# DLOCK.net
KiCad netlist of a schematic drawn in EAGLE
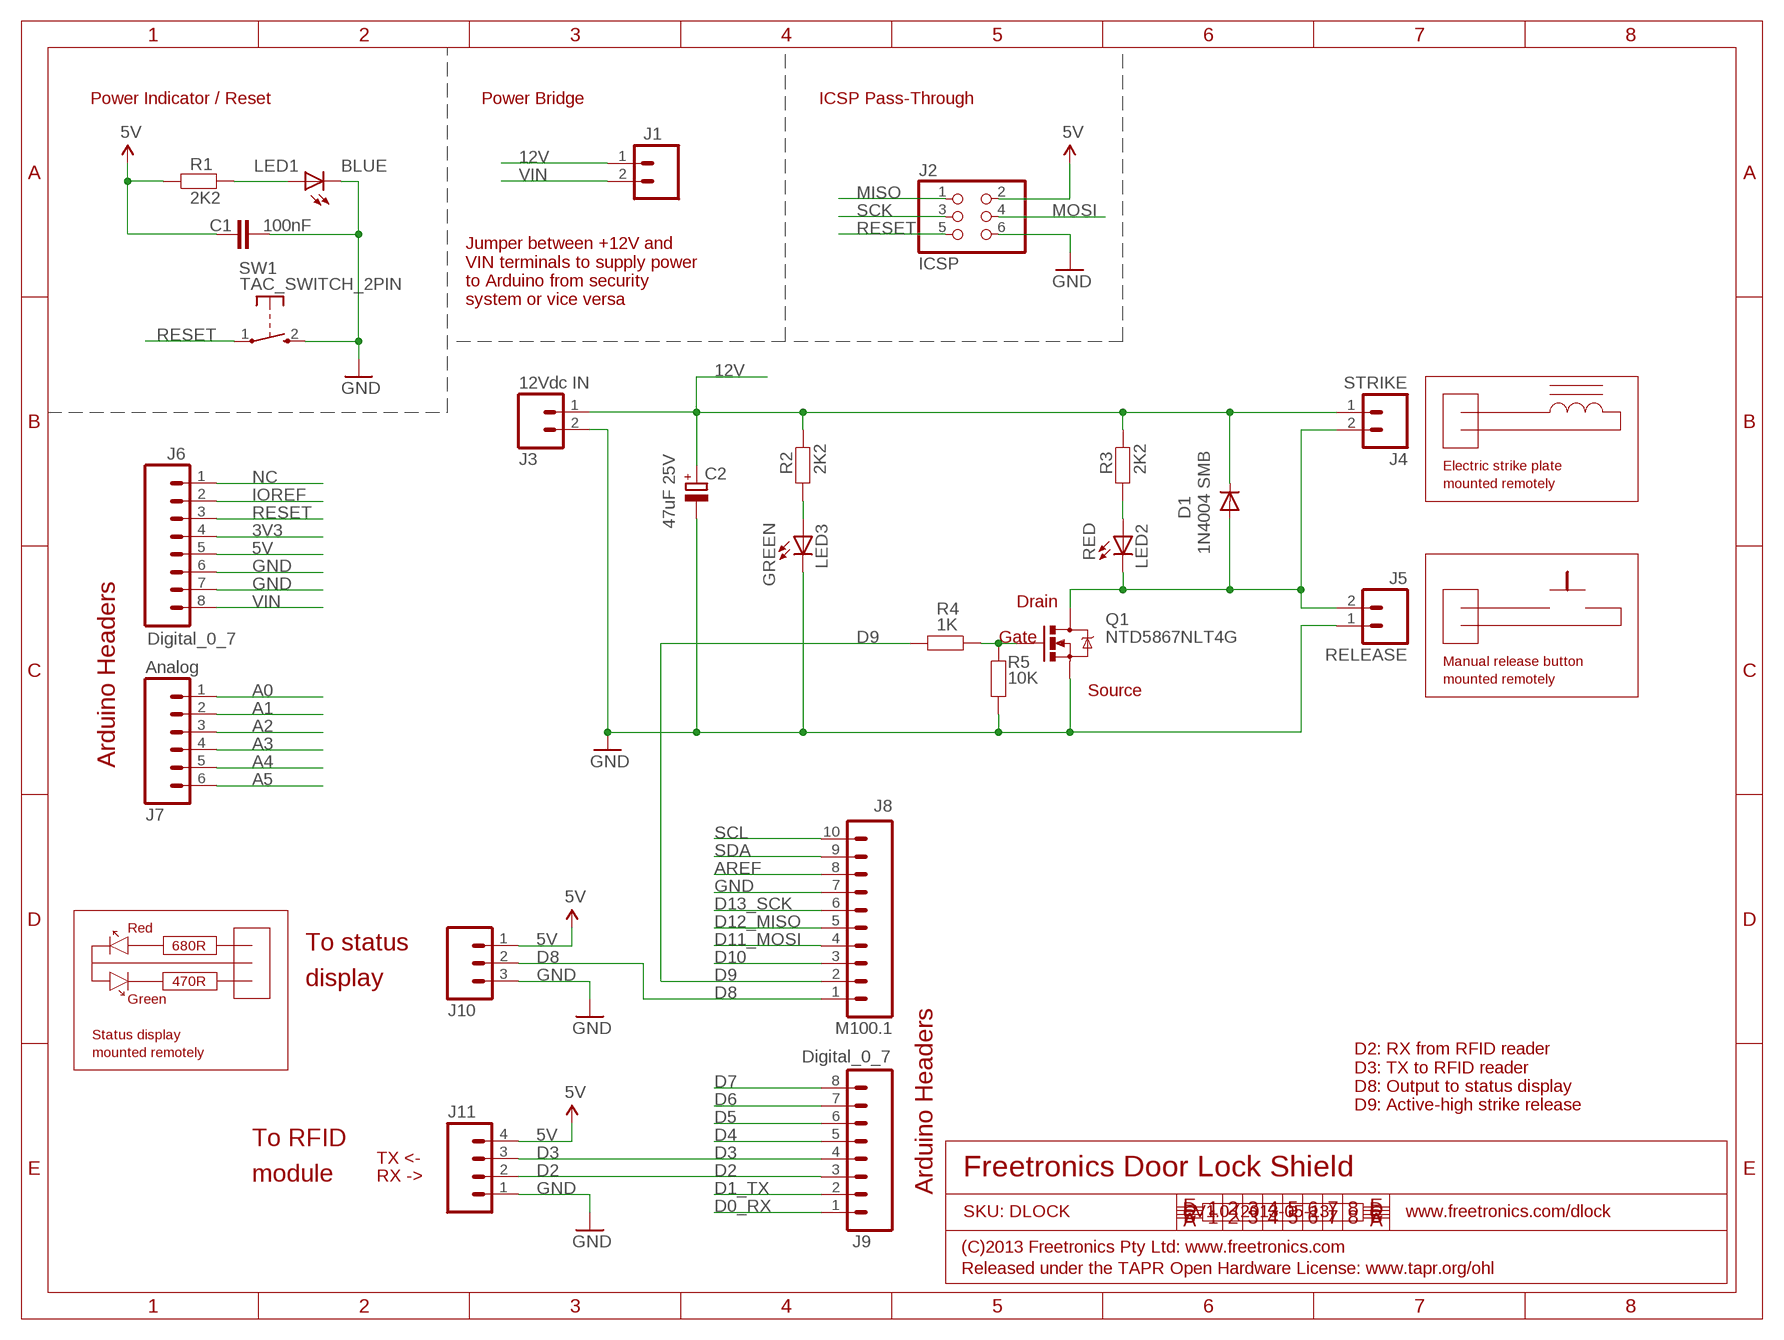
[diagram p0: schematic, sheet 1]

(export (version "E")
  (design (tool "Eeschema 10.0.6"))
  (components
    (comp (ref "C1")
      (value "100nF")
      (footprint "eagle-import:0603")
      (libsource (lib "eagle-import") (part "CAP0603"))
    )
    (comp (ref "C2")
      (value "47uF 25V")
      (footprint "eagle-import:PANASONIC_D")
      (libsource (lib "eagle-import") (part "CPOL-EUD"))
    )
    (comp (ref "D1")
      (value "1N4004 SMB")
      (footprint "eagle-import:SMB-DIODE")
      (libsource (lib "eagle-import") (part "DIODESMB"))
    )
    (comp (ref "J1")
      (value "M02PTH")
      (footprint "eagle-import:1X02")
      (libsource (lib "eagle-import") (part "freetronics-original_M02PTH"))
    )
    (comp (ref "J2")
      (value "ICSP")
      (footprint "eagle-import:2X03")
      (libsource (lib "eagle-import") (part "PINHD-2X3"))
    )
    (comp (ref "J3")
      (value "12Vdc IN")
      (footprint "eagle-import:SCREWTERMINAL-3.5MM-2")
      (libsource (lib "eagle-import") (part "M023.5MM"))
    )
    (comp (ref "J4")
      (value "STRIKE")
      (footprint "eagle-import:SCREWTERMINAL-3.5MM-2")
      (libsource (lib "eagle-import") (part "M023.5MM"))
    )
    (comp (ref "J5")
      (value "RELEASE")
      (footprint "eagle-import:1X02")
      (libsource (lib "eagle-import") (part "M02PTH"))
    )
    (comp (ref "J6")
      (value "Digital_0_7")
      (footprint "eagle-import:1X08")
      (libsource (lib "eagle-import") (part "M08"))
    )
    (comp (ref "J7")
      (value "Analog")
      (footprint "eagle-import:1X06")
      (libsource (lib "eagle-import") (part "M06SIP"))
    )
    (comp (ref "J8")
      (value "M100.1")
      (footprint "eagle-import:1X10")
      (libsource (lib "eagle-import") (part "M100.1"))
    )
    (comp (ref "J9")
      (value "Digital_0_7")
      (footprint "eagle-import:1X08")
      (libsource (lib "eagle-import") (part "M08"))
    )
    (comp (ref "J10")
      (value "M03PTH")
      (footprint "eagle-import:1X03")
      (libsource (lib "eagle-import") (part "M03PTH"))
    )
    (comp (ref "J11")
      (value "M04PTH")
      (footprint "eagle-import:1X04")
      (libsource (lib "eagle-import") (part "M04PTH"))
    )
    (comp (ref "LED1")
      (value "BLUE")
      (footprint "eagle-import:LED-0603")
      (libsource (lib "eagle-import") (part "LED0603"))
    )
    (comp (ref "LED2")
      (value "RED")
      (footprint "eagle-import:LED-0603")
      (libsource (lib "eagle-import") (part "LED0603"))
    )
    (comp (ref "LED3")
      (value "GREEN")
      (footprint "eagle-import:LED-0603")
      (libsource (lib "eagle-import") (part "LED0603"))
    )
    (comp (ref "Q1")
      (value "NTD5867NLT4G")
      (footprint "eagle-import:DPACK")
      (libsource (lib "eagle-import") (part "MOSFET-NCHANNELDPAK"))
    )
    (comp (ref "R1")
      (value "2K2")
      (footprint "eagle-import:0603")
      (libsource (lib "eagle-import") (part "RESISTOR0603"))
    )
    (comp (ref "R2")
      (value "2K2")
      (footprint "eagle-import:0603")
      (libsource (lib "eagle-import") (part "RESISTOR0603"))
    )
    (comp (ref "R3")
      (value "2K2")
      (footprint "eagle-import:0603")
      (libsource (lib "eagle-import") (part "RESISTOR0603"))
    )
    (comp (ref "R4")
      (value "1K")
      (footprint "eagle-import:0603")
      (libsource (lib "eagle-import") (part "freetronics-master-v1_RESISTOR0603"))
    )
    (comp (ref "R5")
      (value "10K")
      (footprint "eagle-import:0603")
      (libsource (lib "eagle-import") (part "freetronics-master-v1_RESISTOR0603"))
    )
    (comp (ref "SW1")
      (value "TAC_SWITCH_2PIN")
      (footprint "eagle-import:TACTILE_SWITCH_SMD_2PIN_TINY")
      (libsource (lib "eagle-import") (part "TAC_SWITCH_2PIN"))
    )
  )
  (nets
    (net (code "1") (name "/3V3") (class "Default")
      (node (ref "J6") (pin "4") (pinfunction "4_4") (pintype "passive"))
    )
    (net (code "2") (name "/12V") (class "Default")
      (node (ref "C2") (pin "+") (pinfunction "+_+") (pintype "passive"))
      (node (ref "D1") (pin "C") (pinfunction "C_C") (pintype "passive"))
      (node (ref "J1") (pin "1") (pinfunction "1_1") (pintype "passive"))
      (node (ref "J3") (pin "1") (pinfunction "1_1") (pintype "passive"))
      (node (ref "J4") (pin "1") (pinfunction "1_1") (pintype "passive"))
      (node (ref "R2") (pin "2") (pinfunction "2_2") (pintype "passive"))
      (node (ref "R3") (pin "2") (pinfunction "2_2") (pintype "passive"))
    )
    (net (code "3") (name "/A0") (class "Default")
      (node (ref "J7") (pin "1") (pinfunction "1_1") (pintype "passive"))
    )
    (net (code "4") (name "/A1") (class "Default")
      (node (ref "J7") (pin "2") (pinfunction "2_2") (pintype "passive"))
    )
    (net (code "5") (name "/A2") (class "Default")
      (node (ref "J7") (pin "3") (pinfunction "3_3") (pintype "passive"))
    )
    (net (code "6") (name "/A3") (class "Default")
      (node (ref "J7") (pin "4") (pinfunction "4_4") (pintype "passive"))
    )
    (net (code "7") (name "/A4") (class "Default")
      (node (ref "J7") (pin "5") (pinfunction "5_5") (pintype "passive"))
    )
    (net (code "8") (name "/A5") (class "Default")
      (node (ref "J7") (pin "6") (pinfunction "6_6") (pintype "passive"))
    )
    (net (code "9") (name "/AREF") (class "Default")
      (node (ref "J8") (pin "8") (pinfunction "8_8") (pintype "passive"))
    )
    (net (code "10") (name "/D0_RX") (class "Default")
      (node (ref "J9") (pin "1") (pinfunction "1_1") (pintype "passive"))
    )
    (net (code "11") (name "/D1_TX") (class "Default")
      (node (ref "J9") (pin "2") (pinfunction "2_2") (pintype "passive"))
    )
    (net (code "12") (name "/D2") (class "Default")
      (node (ref "J11") (pin "2") (pinfunction "2_2") (pintype "passive"))
      (node (ref "J9") (pin "3") (pinfunction "3_3") (pintype "passive"))
    )
    (net (code "13") (name "/D3") (class "Default")
      (node (ref "J11") (pin "3") (pinfunction "3_3") (pintype "passive"))
      (node (ref "J9") (pin "4") (pinfunction "4_4") (pintype "passive"))
    )
    (net (code "14") (name "/D4") (class "Default")
      (node (ref "J9") (pin "5") (pinfunction "5_5") (pintype "passive"))
    )
    (net (code "15") (name "/D5") (class "Default")
      (node (ref "J9") (pin "6") (pinfunction "6_6") (pintype "passive"))
    )
    (net (code "16") (name "/D6") (class "Default")
      (node (ref "J9") (pin "7") (pinfunction "7_7") (pintype "passive"))
    )
    (net (code "17") (name "/D7") (class "Default")
      (node (ref "J9") (pin "8") (pinfunction "8_8") (pintype "passive"))
    )
    (net (code "18") (name "/D8") (class "Default")
      (node (ref "J10") (pin "2") (pinfunction "2_2") (pintype "passive"))
      (node (ref "J8") (pin "1") (pinfunction "1_1") (pintype "passive"))
    )
    (net (code "19") (name "/D9") (class "Default")
      (node (ref "J8") (pin "2") (pinfunction "2_2") (pintype "passive"))
      (node (ref "R4") (pin "2") (pinfunction "2_2") (pintype "passive"))
    )
    (net (code "20") (name "/D10") (class "Default")
      (node (ref "J8") (pin "3") (pinfunction "3_3") (pintype "passive"))
    )
    (net (code "21") (name "/D11_MOSI") (class "Default")
      (node (ref "J8") (pin "4") (pinfunction "4_4") (pintype "passive"))
    )
    (net (code "22") (name "/D12_MISO") (class "Default")
      (node (ref "J8") (pin "5") (pinfunction "5_5") (pintype "passive"))
    )
    (net (code "23") (name "/D13_SCK") (class "Default")
      (node (ref "J8") (pin "6") (pinfunction "6_6") (pintype "passive"))
    )
    (net (code "24") (name "/IOREF") (class "Default")
      (node (ref "J6") (pin "2") (pinfunction "2_2") (pintype "passive"))
    )
    (net (code "25") (name "/MISO") (class "Default")
      (node (ref "J2") (pin "1") (pinfunction "1_1") (pintype "passive"))
    )
    (net (code "26") (name "/MOSI") (class "Default")
      (node (ref "J2") (pin "4") (pinfunction "4_4") (pintype "passive"))
    )
    (net (code "27") (name "/NC") (class "Default")
      (node (ref "J6") (pin "1") (pinfunction "1_1") (pintype "passive"))
    )
    (net (code "28") (name "/RESET") (class "Default")
      (node (ref "J2") (pin "5") (pinfunction "5_5") (pintype "passive"))
      (node (ref "J6") (pin "3") (pinfunction "3_3") (pintype "passive"))
      (node (ref "SW1") (pin "1") (pinfunction "P_1") (pintype "passive"))
    )
    (net (code "29") (name "/SCK") (class "Default")
      (node (ref "J2") (pin "3") (pinfunction "3_3") (pintype "passive"))
    )
    (net (code "30") (name "/SCL") (class "Default")
      (node (ref "J8") (pin "10") (pinfunction "10_10") (pintype "passive"))
    )
    (net (code "31") (name "/SDA") (class "Default")
      (node (ref "J8") (pin "9") (pinfunction "9_9") (pintype "passive"))
    )
    (net (code "32") (name "/VIN") (class "Default")
      (node (ref "J1") (pin "2") (pinfunction "2_2") (pintype "passive"))
      (node (ref "J6") (pin "8") (pinfunction "8_8") (pintype "passive"))
    )
    (net (code "33") (name "5V") (class "Default")
      (node (ref "C1") (pin "1") (pinfunction "1_1") (pintype "passive"))
      (node (ref "J10") (pin "1") (pinfunction "1_1") (pintype "passive"))
      (node (ref "J11") (pin "4") (pinfunction "4_4") (pintype "passive"))
      (node (ref "J2") (pin "2") (pinfunction "2_2") (pintype "passive"))
      (node (ref "J6") (pin "5") (pinfunction "5_5") (pintype "passive"))
      (node (ref "R1") (pin "1") (pinfunction "1_1") (pintype "passive"))
    )
    (net (code "34") (name "GND") (class "Default")
      (node (ref "C1") (pin "2") (pinfunction "2_2") (pintype "passive"))
      (node (ref "C2") (pin "-") (pinfunction "-_-") (pintype "passive"))
      (node (ref "J10") (pin "3") (pinfunction "3_3") (pintype "passive"))
      (node (ref "J11") (pin "1") (pinfunction "1_1") (pintype "passive"))
      (node (ref "J2") (pin "6") (pinfunction "6_6") (pintype "passive"))
      (node (ref "J3") (pin "2") (pinfunction "2_2") (pintype "passive"))
      (node (ref "J5") (pin "1") (pinfunction "1_1") (pintype "passive"))
      (node (ref "J6") (pin "6") (pinfunction "6_6") (pintype "passive"))
      (node (ref "J6") (pin "7") (pinfunction "7_7") (pintype "passive"))
      (node (ref "J8") (pin "7") (pinfunction "7_7") (pintype "passive"))
      (node (ref "LED1") (pin "C") (pinfunction "C_C") (pintype "passive"))
      (node (ref "LED3") (pin "C") (pinfunction "C_C") (pintype "passive"))
      (node (ref "Q1") (pin "3") (pinfunction "S_3") (pintype "passive"))
      (node (ref "R5") (pin "1") (pinfunction "1_1") (pintype "passive"))
      (node (ref "SW1") (pin "2") (pinfunction "S_2") (pintype "passive"))
    )
    (net (code "35") (name "Net-(LED1-PadA)") (class "Default")
      (node (ref "LED1") (pin "A") (pinfunction "A_A") (pintype "passive"))
      (node (ref "R1") (pin "2") (pinfunction "2_2") (pintype "passive"))
    )
    (net (code "36") (name "Net-(LED2-PadA)") (class "Default")
      (node (ref "LED2") (pin "A") (pinfunction "A_A") (pintype "passive"))
      (node (ref "R3") (pin "1") (pinfunction "1_1") (pintype "passive"))
    )
    (net (code "37") (name "Net-(LED3-PadA)") (class "Default")
      (node (ref "LED3") (pin "A") (pinfunction "A_A") (pintype "passive"))
      (node (ref "R2") (pin "1") (pinfunction "1_1") (pintype "passive"))
    )
    (net (code "38") (name "Net-(Q1-D)") (class "Default")
      (node (ref "D1") (pin "A") (pinfunction "A_A") (pintype "passive"))
      (node (ref "J4") (pin "2") (pinfunction "2_2") (pintype "passive"))
      (node (ref "J5") (pin "2") (pinfunction "2_2") (pintype "passive"))
      (node (ref "LED2") (pin "C") (pinfunction "C_C") (pintype "passive"))
      (node (ref "Q1") (pin "2") (pinfunction "D_2") (pintype "passive"))
    )
    (net (code "39") (name "Net-(Q1-G)") (class "Default")
      (node (ref "Q1") (pin "1") (pinfunction "G_1") (pintype "passive"))
      (node (ref "R4") (pin "1") (pinfunction "1_1") (pintype "passive"))
      (node (ref "R5") (pin "2") (pinfunction "2_2") (pintype "passive"))
    )
  )
)
